# MOSFETs_and_Driver.net
KiCad netlist of a schematic drawn in Altium Designer
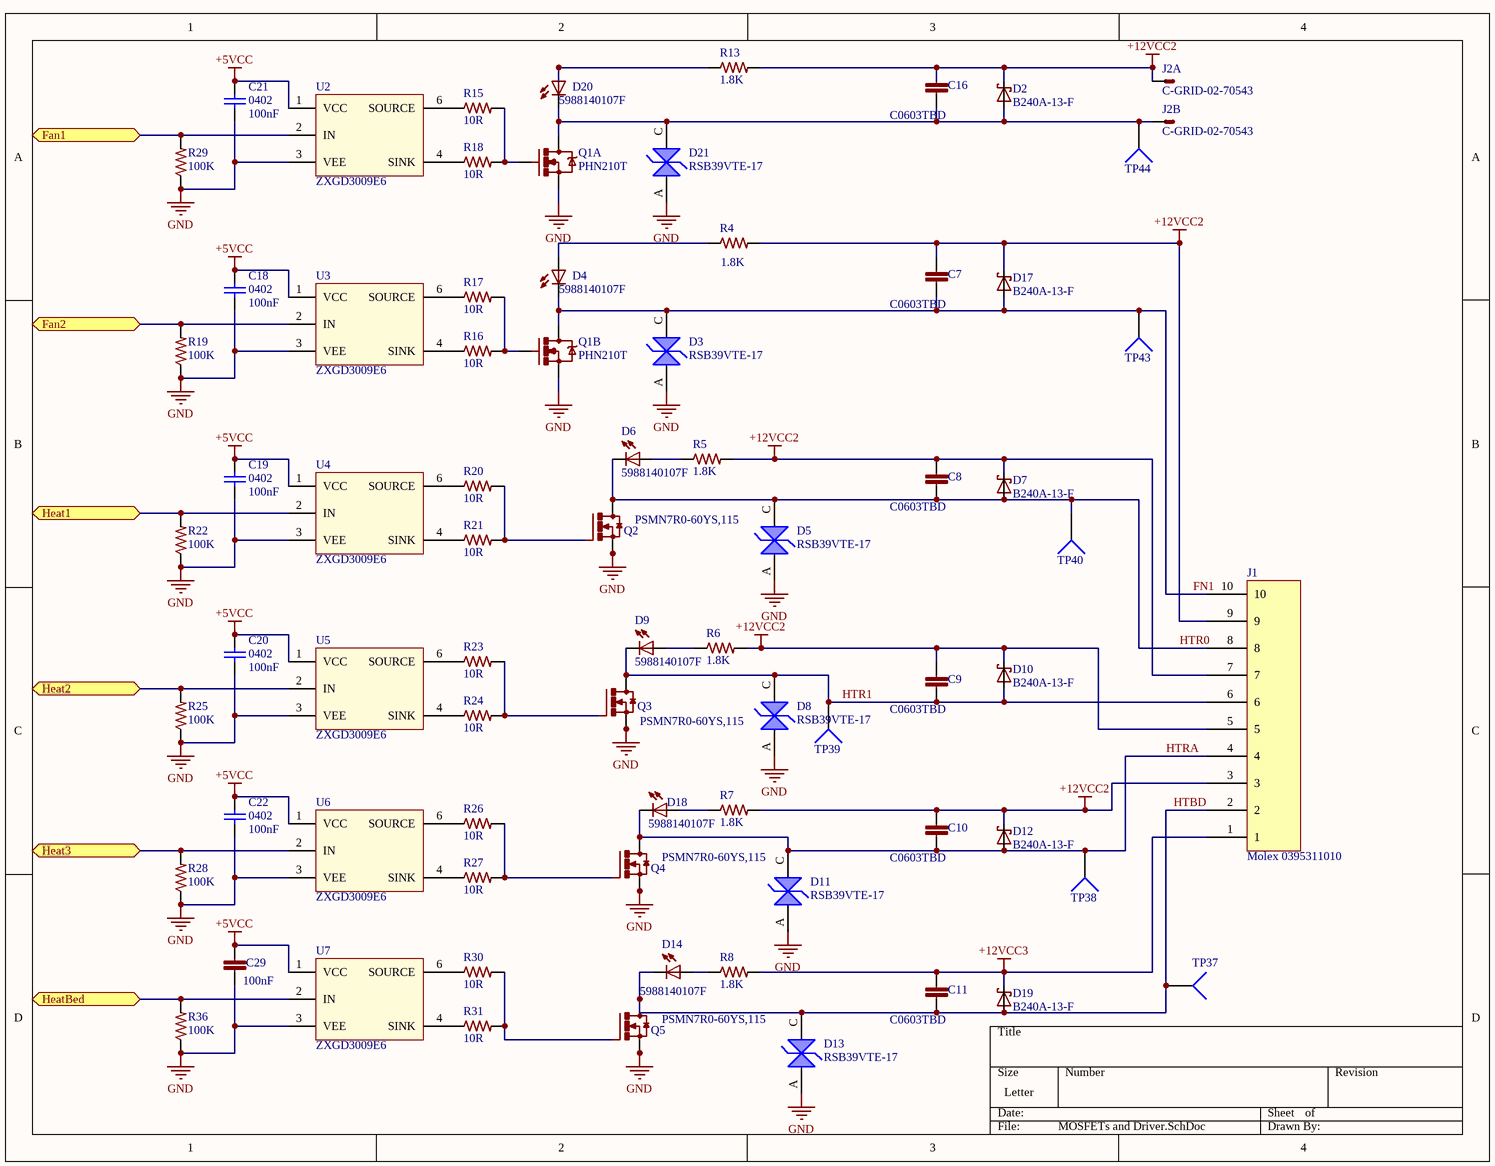
[diagram p0: MOSFETs and Driver.SchDoc]

(export (version "E")
  (design (tool "Eeschema 10.0.6"))
  (components
    (comp (ref "C7")
      (value "C0603TBD")
      (footprint "C0603")
      (description "Capacitor Non Polarized")
      (fields (field (name "PUBLISHER") "UltiMachine"))
      (libsource (lib "3Delight") (part "C0603TBD"))
    )
    (comp (ref "C8")
      (value "C0603TBD")
      (footprint "C0603")
      (description "Capacitor Non Polarized")
      (fields (field (name "PUBLISHER") "UltiMachine"))
      (libsource (lib "3Delight") (part "C0603TBD"))
    )
    (comp (ref "C9")
      (value "C0603TBD")
      (footprint "C0603")
      (description "Capacitor Non Polarized")
      (fields (field (name "PUBLISHER") "UltiMachine"))
      (libsource (lib "3Delight") (part "C0603TBD"))
    )
    (comp (ref "C10")
      (value "C0603TBD")
      (footprint "C0603")
      (description "Capacitor Non Polarized")
      (fields (field (name "PUBLISHER") "UltiMachine"))
      (libsource (lib "3Delight") (part "C0603TBD"))
    )
    (comp (ref "C11")
      (value "C0603TBD")
      (footprint "C0603")
      (description "Capacitor Non Polarized")
      (fields (field (name "PUBLISHER") "UltiMachine"))
      (libsource (lib "3Delight") (part "C0603TBD"))
    )
    (comp (ref "C16")
      (value "C0603TBD")
      (footprint "C0603")
      (description "Capacitor Non Polarized")
      (fields (field (name "PUBLISHER") "UltiMachine"))
      (libsource (lib "3Delight") (part "C0603TBD"))
    )
    (comp (ref "C18")
      (value "100nF")
      (footprint "C0402")
      (description "CAP CER 0.1UF (100nF) 16V 10% X7R 0402")
      (fields
        (field (name "MFR PART #") "GRM155R71C104KA88D")
        (field (name "MFR") "Murata")
        (field (name "PACKAGEREFERENCE") "0402")
        (field (name "PUBLISHER") "Ultimachine")
      )
      (libsource (lib "3Delight") (part "GRM155R71C104KA88D"))
    )
    (comp (ref "C19")
      (value "100nF")
      (footprint "C0402")
      (description "CAP CER 0.1UF (100nF) 16V 10% X7R 0402")
      (fields
        (field (name "MFR PART #") "GRM155R71C104KA88D")
        (field (name "MFR") "Murata")
        (field (name "PACKAGEREFERENCE") "0402")
        (field (name "PUBLISHER") "Ultimachine")
      )
      (libsource (lib "3Delight") (part "GRM155R71C104KA88D"))
    )
    (comp (ref "C20")
      (value "100nF")
      (footprint "C0402")
      (description "CAP CER 0.1UF (100nF) 16V 10% X7R 0402")
      (fields
        (field (name "MFR PART #") "GRM155R71C104KA88D")
        (field (name "MFR") "Murata")
        (field (name "PACKAGEREFERENCE") "0402")
        (field (name "PUBLISHER") "Ultimachine")
      )
      (libsource (lib "3Delight") (part "GRM155R71C104KA88D"))
    )
    (comp (ref "C21")
      (value "100nF")
      (footprint "C0402")
      (description "CAP CER 0.1UF (100nF) 16V 10% X7R 0402")
      (fields
        (field (name "MFR PART #") "GRM155R71C104KA88D")
        (field (name "MFR") "Murata")
        (field (name "PACKAGEREFERENCE") "0402")
        (field (name "PUBLISHER") "Ultimachine")
      )
      (libsource (lib "3Delight") (part "GRM155R71C104KA88D"))
    )
    (comp (ref "C22")
      (value "100nF")
      (footprint "C0402")
      (description "CAP CER 0.1UF (100nF) 16V 10% X7R 0402")
      (fields
        (field (name "MFR PART #") "GRM155R71C104KA88D")
        (field (name "MFR") "Murata")
        (field (name "PACKAGEREFERENCE") "0402")
        (field (name "PUBLISHER") "Ultimachine")
      )
      (libsource (lib "3Delight") (part "GRM155R71C104KA88D"))
    )
    (comp (ref "C29")
      (value "100nF")
      (footprint "C0402")
      (description "CAP CER 0402 100nF 16V 10% X7R")
      (fields
        (field (name "MANUFACTURERPARTNUMBER") "GRM155R71C104KA88D")
        (field (name "PUBLISHER") "UltiMachine")
      )
      (libsource (lib "") (part "GRM155R71C104KA88D_1"))
    )
    (comp (ref "D2")
      (value "B240A-13-F")
      (footprint "SMA-SM")
      (description "DIODE Schottky 3A SMA")
      (fields (field (name "MANUFACTURERPARTNUMBER") "SK310A") (field (name "PUBLISHER") "UltiMachine"))
      (libsource (lib "3Delight") (part "SK310A"))
    )
    (comp (ref "D3")
      (value "RSB39VTE-17")
      (footprint "SOD323-R")
      (description "DIODE TVS")
      (libsource (lib "3Delight") (part "RSB39VTE-17"))
    )
    (comp (ref "D4")
      (value "5988140107F")
      (footprint "LED2012120")
      (description "LED 0805 Yellow")
      (fields (field (name "PUBLISHER") "UltiMachine"))
      (libsource (lib "3Delight") (part "5988140107F"))
    )
    (comp (ref "D5")
      (value "RSB39VTE-17")
      (footprint "SOD323-R")
      (description "DIODE TVS")
      (libsource (lib "3Delight") (part "RSB39VTE-17"))
    )
    (comp (ref "D6")
      (value "5988140107F")
      (footprint "LED2012120")
      (description "LED 0805 Yellow")
      (fields (field (name "PUBLISHER") "UltiMachine"))
      (libsource (lib "3Delight") (part "5988140107F"))
    )
    (comp (ref "D7")
      (value "B240A-13-F")
      (footprint "SMA-SM")
      (description "DIODE Schottky 3A SMA")
      (fields (field (name "MANUFACTURERPARTNUMBER") "SK310A") (field (name "PUBLISHER") "UltiMachine"))
      (libsource (lib "3Delight") (part "SK310A"))
    )
    (comp (ref "D8")
      (value "RSB39VTE-17")
      (footprint "SOD323-R")
      (description "DIODE TVS")
      (libsource (lib "3Delight") (part "RSB39VTE-17"))
    )
    (comp (ref "D9")
      (value "5988140107F")
      (footprint "LED2012120")
      (description "LED 0805 Yellow")
      (fields (field (name "PUBLISHER") "UltiMachine"))
      (libsource (lib "3Delight") (part "5988140107F"))
    )
    (comp (ref "D10")
      (value "B240A-13-F")
      (footprint "SMA-SM")
      (description "DIODE Schottky 3A SMA")
      (fields (field (name "MANUFACTURERPARTNUMBER") "SK310A") (field (name "PUBLISHER") "UltiMachine"))
      (libsource (lib "3Delight") (part "SK310A"))
    )
    (comp (ref "D11")
      (value "RSB39VTE-17")
      (footprint "SOD323-R")
      (description "DIODE TVS")
      (libsource (lib "3Delight") (part "RSB39VTE-17"))
    )
    (comp (ref "D12")
      (value "B240A-13-F")
      (footprint "SMA-SM")
      (description "DIODE Schottky 3A SMA")
      (fields (field (name "MANUFACTURERPARTNUMBER") "SK310A") (field (name "PUBLISHER") "UltiMachine"))
      (libsource (lib "3Delight") (part "SK310A"))
    )
    (comp (ref "D13")
      (value "RSB39VTE-17")
      (footprint "SOD323-R")
      (description "DIODE TVS")
      (libsource (lib "3Delight") (part "RSB39VTE-17"))
    )
    (comp (ref "D14")
      (value "5988140107F")
      (footprint "LED2012120")
      (description "LED 0805 Yellow")
      (fields (field (name "PUBLISHER") "UltiMachine"))
      (libsource (lib "3Delight") (part "5988140107F"))
    )
    (comp (ref "D17")
      (value "B240A-13-F")
      (footprint "SMA-SM")
      (description "DIODE Schottky 3A SMA")
      (fields (field (name "MANUFACTURERPARTNUMBER") "SK310A") (field (name "PUBLISHER") "UltiMachine"))
      (libsource (lib "3Delight") (part "SK310A"))
    )
    (comp (ref "D18")
      (value "5988140107F")
      (footprint "LED2012120")
      (description "LED 0805 Yellow")
      (fields (field (name "PUBLISHER") "UltiMachine"))
      (libsource (lib "3Delight") (part "5988140107F"))
    )
    (comp (ref "D19")
      (value "B240A-13-F")
      (footprint "SMA-SM")
      (description "DIODE Schottky 3A SMA")
      (fields (field (name "MANUFACTURERPARTNUMBER") "SK310A") (field (name "PUBLISHER") "UltiMachine"))
      (libsource (lib "3Delight") (part "SK310A"))
    )
    (comp (ref "D20")
      (value "5988140107F")
      (footprint "LED2012120")
      (description "LED 0805 Yellow")
      (fields (field (name "PUBLISHER") "UltiMachine"))
      (libsource (lib "3Delight") (part "5988140107F"))
    )
    (comp (ref "D21")
      (value "RSB39VTE-17")
      (footprint "SOD323-R")
      (description "DIODE TVS")
      (libsource (lib "3Delight") (part "RSB39VTE-17"))
    )
    (comp (ref "J1")
      (value "Molex 0395311010")
      (footprint "MSTBV10")
      (description "MSBTV10 10 port connector same as RAMBo")
      (fields (field (name "PART NUMBER") "0395311010"))
      (libsource (lib "Tigershark3D") (part "0395311010 - Molex 10 Position Connector"))
    )
    (comp (ref "J2")
      (value "C-GRID-02-70543")
      (footprint "70543-02")
      (description "Connector 2pos")
      (fields (field (name "PUBLISHER") "UltiMachine"))
      (libsource (lib "3Delight") (part "C-GRID-02-70543"))
    )
    (comp (ref "Q1")
      (value "PHN210T")
      (footprint "SOIC8-dual-drain")
      (description "Dual N-channel TrenchMOS intermediate level FET")
      (libsource (lib "3Delight") (part "PHN210T"))
    )
    (comp (ref "Q2")
      (value "PSMN7R0-60YS,115")
      (footprint "SOT669")
      (description "Mosfet N-channel 60V 356A 117W 9.3mOhms")
      (fields (field (name "PUBLISHER") "UltiMachine"))
      (libsource (lib "3Delight") (part "PSMN7R0-60YS,115"))
    )
    (comp (ref "Q3")
      (value "PSMN7R0-60YS,115")
      (footprint "SOT669")
      (description "Mosfet N-channel 60V 356A 117W 9.3mOhms")
      (fields (field (name "PUBLISHER") "UltiMachine"))
      (libsource (lib "3Delight") (part "PSMN7R0-60YS,115"))
    )
    (comp (ref "Q4")
      (value "PSMN7R0-60YS,115")
      (footprint "SOT669")
      (description "Mosfet N-channel 60V 356A 117W 9.3mOhms")
      (fields (field (name "PUBLISHER") "UltiMachine"))
      (libsource (lib "3Delight") (part "PSMN7R0-60YS,115"))
    )
    (comp (ref "Q5")
      (value "PSMN7R0-60YS,115")
      (footprint "SOT669")
      (description "Mosfet N-channel 60V 356A 117W 9.3mOhms")
      (fields (field (name "PUBLISHER") "UltiMachine"))
      (libsource (lib "3Delight") (part "PSMN7R0-60YS,115"))
    )
    (comp (ref "R4")
      (value "1.8K")
      (footprint "R0603")
      (description "RES 0603 1.8K 100mW 5%")
      (fields
        (field (name "MANUFACTURERPARTNUMBER") "RC0603JR-071K8L")
        (field (name "PUBLISHER") "UltiMachine")
      )
      (libsource (lib "3Delight") (part "RC0603JR-071K8L"))
    )
    (comp (ref "R5")
      (value "1.8K")
      (footprint "R0603")
      (description "RES 0603 1.8K 100mW 5%")
      (fields
        (field (name "MANUFACTURERPARTNUMBER") "RC0603JR-071K8L")
        (field (name "PUBLISHER") "UltiMachine")
      )
      (libsource (lib "3Delight") (part "RC0603JR-071K8L"))
    )
    (comp (ref "R6")
      (value "1.8K")
      (footprint "R0603")
      (description "RES 0603 1.8K 100mW 5%")
      (fields
        (field (name "MANUFACTURERPARTNUMBER") "RC0603JR-071K8L")
        (field (name "PUBLISHER") "UltiMachine")
      )
      (libsource (lib "3Delight") (part "RC0603JR-071K8L"))
    )
    (comp (ref "R7")
      (value "1.8K")
      (footprint "R0603")
      (description "RES 0603 1.8K 100mW 5%")
      (fields
        (field (name "MANUFACTURERPARTNUMBER") "RC0603JR-071K8L")
        (field (name "PUBLISHER") "UltiMachine")
      )
      (libsource (lib "3Delight") (part "RC0603JR-071K8L"))
    )
    (comp (ref "R8")
      (value "1.8K")
      (footprint "R0603")
      (description "RES 0603 1.8K 100mW 5%")
      (fields
        (field (name "MANUFACTURERPARTNUMBER") "RC0603JR-071K8L")
        (field (name "PUBLISHER") "UltiMachine")
      )
      (libsource (lib "3Delight") (part "RC0603JR-071K8L"))
    )
    (comp (ref "R13")
      (value "1.8K")
      (footprint "R0603")
      (description "RES 0603 1.8K 100mW 5%")
      (fields
        (field (name "MANUFACTURERPARTNUMBER") "RC0603JR-071K8L")
        (field (name "PUBLISHER") "UltiMachine")
      )
      (libsource (lib "3Delight") (part "RC0603JR-071K8L"))
    )
    (comp (ref "R15")
      (value "10R")
      (footprint "R0402")
      (description "RES SMD 10K OHM 1% 1/16W 0402")
      (fields
        (field (name "MANUFACTURERPARTNUMBER") "RC0402FR-0710KP")
        (field (name "PUBLISHER") "UltiMachine")
      )
      (libsource (lib "3Delight") (part "RC0402FR-0710RL"))
    )
    (comp (ref "R16")
      (value "10R")
      (footprint "R0402")
      (description "RES SMD 10K OHM 1% 1/16W 0402")
      (fields
        (field (name "MANUFACTURERPARTNUMBER") "RC0402FR-0710KP")
        (field (name "PUBLISHER") "UltiMachine")
      )
      (libsource (lib "3Delight") (part "RC0402FR-0710RL"))
    )
    (comp (ref "R17")
      (value "10R")
      (footprint "R0402")
      (description "RES SMD 10K OHM 1% 1/16W 0402")
      (fields
        (field (name "MANUFACTURERPARTNUMBER") "RC0402FR-0710KP")
        (field (name "PUBLISHER") "UltiMachine")
      )
      (libsource (lib "3Delight") (part "RC0402FR-0710RL"))
    )
    (comp (ref "R18")
      (value "10R")
      (footprint "R0402")
      (description "RES SMD 10K OHM 1% 1/16W 0402")
      (fields
        (field (name "MANUFACTURERPARTNUMBER") "RC0402FR-0710KP")
        (field (name "PUBLISHER") "UltiMachine")
      )
      (libsource (lib "3Delight") (part "RC0402FR-0710RL"))
    )
    (comp (ref "R19")
      (value "100K")
      (footprint "3Delight:R0402")
      (description "RES SMD 100K OHM 1% 1/16W 0402")
      (fields
        (field (name "MANUFACTURER") "Samsung")
        (field (name "MANUFACTURERPARTNUMBER") "RC1005F104CS")
        (field (name "PUBLISHER") "UltiMachine")
      )
      (libsource (lib "Tigershark3D") (part "RC1005F104CS"))
    )
    (comp (ref "R20")
      (value "10R")
      (footprint "R0402")
      (description "RES SMD 10K OHM 1% 1/16W 0402")
      (fields
        (field (name "MANUFACTURERPARTNUMBER") "RC0402FR-0710KP")
        (field (name "PUBLISHER") "UltiMachine")
      )
      (libsource (lib "3Delight") (part "RC0402FR-0710RL"))
    )
    (comp (ref "R21")
      (value "10R")
      (footprint "R0402")
      (description "RES SMD 10K OHM 1% 1/16W 0402")
      (fields
        (field (name "MANUFACTURERPARTNUMBER") "RC0402FR-0710KP")
        (field (name "PUBLISHER") "UltiMachine")
      )
      (libsource (lib "3Delight") (part "RC0402FR-0710RL"))
    )
    (comp (ref "R22")
      (value "100K")
      (footprint "3Delight:R0402")
      (description "RES SMD 100K OHM 1% 1/16W 0402")
      (fields
        (field (name "MANUFACTURER") "Samsung")
        (field (name "MANUFACTURERPARTNUMBER") "RC1005F104CS")
        (field (name "PUBLISHER") "UltiMachine")
      )
      (libsource (lib "Tigershark3D") (part "RC1005F104CS"))
    )
    (comp (ref "R23")
      (value "10R")
      (footprint "R0402")
      (description "RES SMD 10K OHM 1% 1/16W 0402")
      (fields
        (field (name "MANUFACTURERPARTNUMBER") "RC0402FR-0710KP")
        (field (name "PUBLISHER") "UltiMachine")
      )
      (libsource (lib "3Delight") (part "RC0402FR-0710RL"))
    )
    (comp (ref "R24")
      (value "10R")
      (footprint "R0402")
      (description "RES SMD 10K OHM 1% 1/16W 0402")
      (fields
        (field (name "MANUFACTURERPARTNUMBER") "RC0402FR-0710KP")
        (field (name "PUBLISHER") "UltiMachine")
      )
      (libsource (lib "3Delight") (part "RC0402FR-0710RL"))
    )
    (comp (ref "R25")
      (value "100K")
      (footprint "3Delight:R0402")
      (description "RES SMD 100K OHM 1% 1/16W 0402")
      (fields
        (field (name "MANUFACTURER") "Samsung")
        (field (name "MANUFACTURERPARTNUMBER") "RC1005F104CS")
        (field (name "PUBLISHER") "UltiMachine")
      )
      (libsource (lib "Tigershark3D") (part "RC1005F104CS"))
    )
    (comp (ref "R26")
      (value "10R")
      (footprint "R0402")
      (description "RES SMD 10K OHM 1% 1/16W 0402")
      (fields
        (field (name "MANUFACTURERPARTNUMBER") "RC0402FR-0710KP")
        (field (name "PUBLISHER") "UltiMachine")
      )
      (libsource (lib "3Delight") (part "RC0402FR-0710RL"))
    )
    (comp (ref "R27")
      (value "10R")
      (footprint "R0402")
      (description "RES SMD 10K OHM 1% 1/16W 0402")
      (fields
        (field (name "MANUFACTURERPARTNUMBER") "RC0402FR-0710KP")
        (field (name "PUBLISHER") "UltiMachine")
      )
      (libsource (lib "3Delight") (part "RC0402FR-0710RL"))
    )
    (comp (ref "R28")
      (value "100K")
      (footprint "3Delight:R0402")
      (description "RES SMD 100K OHM 1% 1/16W 0402")
      (fields
        (field (name "MANUFACTURER") "Samsung")
        (field (name "MANUFACTURERPARTNUMBER") "RC1005F104CS")
        (field (name "PUBLISHER") "UltiMachine")
      )
      (libsource (lib "Tigershark3D") (part "RC1005F104CS"))
    )
    (comp (ref "R29")
      (value "100K")
      (footprint "3Delight:R0402")
      (description "RES SMD 100K OHM 1% 1/16W 0402")
      (fields
        (field (name "MANUFACTURER") "Samsung")
        (field (name "MANUFACTURERPARTNUMBER") "RC1005F104CS")
        (field (name "PUBLISHER") "UltiMachine")
      )
      (libsource (lib "Tigershark3D") (part "RC1005F104CS"))
    )
    (comp (ref "R30")
      (value "10R")
      (footprint "R0402")
      (description "RES SMD 10K OHM 1% 1/16W 0402")
      (fields
        (field (name "MANUFACTURERPARTNUMBER") "RC0402FR-0710KP")
        (field (name "PUBLISHER") "UltiMachine")
      )
      (libsource (lib "3Delight") (part "RC0402FR-0710RL"))
    )
    (comp (ref "R31")
      (value "10R")
      (footprint "R0402")
      (description "RES SMD 10K OHM 1% 1/16W 0402")
      (fields
        (field (name "MANUFACTURERPARTNUMBER") "RC0402FR-0710KP")
        (field (name "PUBLISHER") "UltiMachine")
      )
      (libsource (lib "3Delight") (part "RC0402FR-0710RL"))
    )
    (comp (ref "R36")
      (value "100K")
      (footprint "R0402")
      (description "RES SMD 100K OHM 1% 1/16W 0402")
      (fields
        (field (name "MANUFACTURER") "Samsung")
        (field (name "MANUFACTURERPARTNUMBER") "RC1005F104CS")
        (field (name "PUBLISHER") "UltiMachine")
      )
      (libsource (lib "Tigershark3D") (part "RC1005F104CS"))
    )
    (comp (ref "TP37")
      (value "TP4")
      (footprint "TP-2")
      (description "Socket")
      (fields (field (name "PUBLISHER") "Altium Limited"))
      (libsource (lib "ZMBo Schematic Library") (part "Socket"))
    )
    (comp (ref "TP38")
      (value "TP4")
      (footprint "TP-2")
      (description "Socket")
      (fields (field (name "PUBLISHER") "Altium Limited"))
      (libsource (lib "ZMBo Schematic Library") (part "Socket"))
    )
    (comp (ref "TP39")
      (value "TP4")
      (footprint "TP-2")
      (description "Socket")
      (fields (field (name "PUBLISHER") "Altium Limited"))
      (libsource (lib "ZMBo Schematic Library") (part "Socket"))
    )
    (comp (ref "TP40")
      (value "TP4")
      (footprint "TP-2")
      (description "Socket")
      (fields (field (name "PUBLISHER") "Altium Limited"))
      (libsource (lib "ZMBo Schematic Library") (part "Socket"))
    )
    (comp (ref "TP43")
      (value "TP4")
      (footprint "TP-2")
      (description "Socket")
      (fields (field (name "PUBLISHER") "Altium Limited"))
      (libsource (lib "ZMBo Schematic Library") (part "Socket"))
    )
    (comp (ref "TP44")
      (value "TP4")
      (footprint "TP-2")
      (description "Socket")
      (fields (field (name "PUBLISHER") "Altium Limited"))
      (libsource (lib "ZMBo Schematic Library") (part "Socket"))
    )
    (comp (ref "U2")
      (value "ZXGD3009E6")
      (footprint "SOT26P285X140-6L")
      (description "MOSFET DRVR 3A 1-OUT High Speed Non-Inv6-Pin SOT-26 T/R")
      (libsource (lib "3Delight") (part "ZXGD3009E6"))
    )
    (comp (ref "U3")
      (value "ZXGD3009E6")
      (footprint "SOT26P285X140-6L")
      (description "MOSFET DRVR 3A 1-OUT High Speed Non-Inv6-Pin SOT-26 T/R")
      (libsource (lib "3Delight") (part "ZXGD3009E6"))
    )
    (comp (ref "U4")
      (value "ZXGD3009E6")
      (footprint "SOT26P285X140-6L")
      (description "MOSFET DRVR 3A 1-OUT High Speed Non-Inv6-Pin SOT-26 T/R")
      (libsource (lib "3Delight") (part "ZXGD3009E6"))
    )
    (comp (ref "U5")
      (value "ZXGD3009E6")
      (footprint "SOT26P285X140-6L")
      (description "MOSFET DRVR 3A 1-OUT High Speed Non-Inv6-Pin SOT-26 T/R")
      (libsource (lib "3Delight") (part "ZXGD3009E6"))
    )
    (comp (ref "U6")
      (value "ZXGD3009E6")
      (footprint "SOT26P285X140-6L")
      (description "MOSFET DRVR 3A 1-OUT High Speed Non-Inv6-Pin SOT-26 T/R")
      (libsource (lib "3Delight") (part "ZXGD3009E6"))
    )
    (comp (ref "U7")
      (value "ZXGD3009E6")
      (footprint "SOT26P285X140-6L")
      (description "MOSFET DRVR 3A 1-OUT High Speed Non-Inv6-Pin SOT-26 T/R")
      (libsource (lib "3Delight") (part "ZXGD3009E6"))
    )
  )
  (nets
    (net (code "1") (name "+5VCC") (class "Default")
      (node (ref "C18") (pin "2") (pinfunction "2_2") (pintype "passive"))
      (node (ref "C19") (pin "2") (pinfunction "2_2") (pintype "passive"))
      (node (ref "C20") (pin "2") (pinfunction "2_2") (pintype "passive"))
      (node (ref "C21") (pin "2") (pinfunction "2_2") (pintype "passive"))
      (node (ref "C22") (pin "2") (pinfunction "2_2") (pintype "passive"))
      (node (ref "C29") (pin "1") (pinfunction "1_1") (pintype "passive"))
      (node (ref "U2") (pin "1") (pinfunction "VCC_1") (pintype "power_in"))
      (node (ref "U3") (pin "1") (pinfunction "VCC_1") (pintype "power_in"))
      (node (ref "U4") (pin "1") (pinfunction "VCC_1") (pintype "power_in"))
      (node (ref "U5") (pin "1") (pinfunction "VCC_1") (pintype "power_in"))
      (node (ref "U6") (pin "1") (pinfunction "VCC_1") (pintype "power_in"))
      (node (ref "U7") (pin "1") (pinfunction "VCC_1") (pintype "power_in"))
    )
    (net (code "2") (name "+12VCC2") (class "Default")
      (node (ref "C10") (pin "1") (pinfunction "1_1") (pintype "passive"))
      (node (ref "C16") (pin "1") (pinfunction "1_1") (pintype "passive"))
      (node (ref "C7") (pin "1") (pinfunction "1_1") (pintype "passive"))
      (node (ref "C8") (pin "1") (pinfunction "1_1") (pintype "passive"))
      (node (ref "C9") (pin "1") (pinfunction "1_1") (pintype "passive"))
      (node (ref "D10") (pin "C") (pinfunction "C_C") (pintype "passive"))
      (node (ref "D12") (pin "C") (pinfunction "C_C") (pintype "passive"))
      (node (ref "D17") (pin "C") (pinfunction "C_C") (pintype "passive"))
      (node (ref "D2") (pin "C") (pinfunction "C_C") (pintype "passive"))
      (node (ref "D7") (pin "C") (pinfunction "C_C") (pintype "passive"))
      (node (ref "J1") (pin "3") (pinfunction "3_3") (pintype "passive"))
      (node (ref "J1") (pin "5") (pinfunction "5_5") (pintype "passive"))
      (node (ref "J1") (pin "7") (pinfunction "7_7") (pintype "passive"))
      (node (ref "J1") (pin "9") (pinfunction "9_9") (pintype "passive"))
      (node (ref "J2") (pin "1") (pinfunction "S_1") (pintype "passive"))
      (node (ref "R13") (pin "2") (pinfunction "2_2") (pintype "passive"))
      (node (ref "R4") (pin "2") (pinfunction "2_2") (pintype "passive"))
      (node (ref "R5") (pin "2") (pinfunction "2_2") (pintype "passive"))
      (node (ref "R6") (pin "2") (pinfunction "2_2") (pintype "passive"))
      (node (ref "R7") (pin "2") (pinfunction "2_2") (pintype "passive"))
    )
    (net (code "3") (name "+12VCC3") (class "Default")
      (node (ref "C11") (pin "1") (pinfunction "1_1") (pintype "passive"))
      (node (ref "D19") (pin "C") (pinfunction "C_C") (pintype "passive"))
      (node (ref "J1") (pin "1") (pinfunction "1_1") (pintype "passive"))
      (node (ref "R8") (pin "2") (pinfunction "2_2") (pintype "passive"))
    )
    (net (code "4") (name "/FN1") (class "Default")
      (node (ref "C7") (pin "2") (pinfunction "2_2") (pintype "passive"))
      (node (ref "D17") (pin "A") (pinfunction "A_A") (pintype "passive"))
      (node (ref "D3") (pin "C") (pinfunction "C_C") (pintype "power_in"))
      (node (ref "D4") (pin "C") (pinfunction "C_C") (pintype "passive"))
      (node (ref "J1") (pin "10") (pinfunction "10_10") (pintype "passive"))
      (node (ref "Q1") (pin "5") (pinfunction "D_5") (pintype "passive"))
      (node (ref "TP43") (pin "1") (pinfunction "1_1") (pintype "passive"))
    )
    (net (code "5") (name "/Fan1") (class "Default")
      (node (ref "R29") (pin "2") (pinfunction "2_2") (pintype "passive"))
      (node (ref "U2") (pin "2") (pinfunction "IN_2") (pintype "power_in"))
    )
    (net (code "6") (name "/Fan2") (class "Default")
      (node (ref "R19") (pin "2") (pinfunction "2_2") (pintype "passive"))
      (node (ref "U3") (pin "2") (pinfunction "IN_2") (pintype "power_in"))
    )
    (net (code "7") (name "/HTBD") (class "Default")
      (node (ref "C11") (pin "2") (pinfunction "2_2") (pintype "passive"))
      (node (ref "D13") (pin "C") (pinfunction "C_C") (pintype "power_in"))
      (node (ref "D14") (pin "C") (pinfunction "C_C") (pintype "passive"))
      (node (ref "D19") (pin "A") (pinfunction "A_A") (pintype "passive"))
      (node (ref "J1") (pin "2") (pinfunction "2_2") (pintype "passive"))
      (node (ref "Q5") (pin "MB") (pinfunction "D_MB") (pintype "passive"))
      (node (ref "TP37") (pin "1") (pinfunction "1_1") (pintype "passive"))
    )
    (net (code "8") (name "/HTR0") (class "Default")
      (node (ref "C8") (pin "2") (pinfunction "2_2") (pintype "passive"))
      (node (ref "D5") (pin "C") (pinfunction "C_C") (pintype "power_in"))
      (node (ref "D6") (pin "C") (pinfunction "C_C") (pintype "passive"))
      (node (ref "D7") (pin "A") (pinfunction "A_A") (pintype "passive"))
      (node (ref "J1") (pin "8") (pinfunction "8_8") (pintype "passive"))
      (node (ref "Q2") (pin "MB") (pinfunction "D_MB") (pintype "passive"))
      (node (ref "TP40") (pin "1") (pinfunction "1_1") (pintype "passive"))
    )
    (net (code "9") (name "/HTR1") (class "Default")
      (node (ref "C9") (pin "2") (pinfunction "2_2") (pintype "passive"))
      (node (ref "D10") (pin "A") (pinfunction "A_A") (pintype "passive"))
      (node (ref "D8") (pin "C") (pinfunction "C_C") (pintype "power_in"))
      (node (ref "D9") (pin "C") (pinfunction "C_C") (pintype "passive"))
      (node (ref "J1") (pin "6") (pinfunction "6_6") (pintype "passive"))
      (node (ref "Q3") (pin "MB") (pinfunction "D_MB") (pintype "passive"))
      (node (ref "TP39") (pin "1") (pinfunction "1_1") (pintype "passive"))
    )
    (net (code "10") (name "/HTRA") (class "Default")
      (node (ref "C10") (pin "2") (pinfunction "2_2") (pintype "passive"))
      (node (ref "D11") (pin "C") (pinfunction "C_C") (pintype "power_in"))
      (node (ref "D12") (pin "A") (pinfunction "A_A") (pintype "passive"))
      (node (ref "D18") (pin "C") (pinfunction "C_C") (pintype "passive"))
      (node (ref "J1") (pin "4") (pinfunction "4_4") (pintype "passive"))
      (node (ref "Q4") (pin "MB") (pinfunction "D_MB") (pintype "passive"))
      (node (ref "TP38") (pin "1") (pinfunction "1_1") (pintype "passive"))
    )
    (net (code "11") (name "/Heat1") (class "Default")
      (node (ref "R22") (pin "2") (pinfunction "2_2") (pintype "passive"))
      (node (ref "U4") (pin "2") (pinfunction "IN_2") (pintype "power_in"))
    )
    (net (code "12") (name "/Heat2") (class "Default")
      (node (ref "R25") (pin "2") (pinfunction "2_2") (pintype "passive"))
      (node (ref "U5") (pin "2") (pinfunction "IN_2") (pintype "power_in"))
    )
    (net (code "13") (name "/Heat3") (class "Default")
      (node (ref "R28") (pin "2") (pinfunction "2_2") (pintype "passive"))
      (node (ref "U6") (pin "2") (pinfunction "IN_2") (pintype "power_in"))
    )
    (net (code "14") (name "/HeatBed") (class "Default")
      (node (ref "R36") (pin "2") (pinfunction "2_2") (pintype "passive"))
      (node (ref "U7") (pin "2") (pinfunction "IN_2") (pintype "power_in"))
    )
    (net (code "15") (name "GND") (class "Default")
      (node (ref "C18") (pin "1") (pinfunction "1_1") (pintype "passive"))
      (node (ref "C19") (pin "1") (pinfunction "1_1") (pintype "passive"))
      (node (ref "C20") (pin "1") (pinfunction "1_1") (pintype "passive"))
      (node (ref "C21") (pin "1") (pinfunction "1_1") (pintype "passive"))
      (node (ref "C22") (pin "1") (pinfunction "1_1") (pintype "passive"))
      (node (ref "C29") (pin "2") (pinfunction "2_2") (pintype "passive"))
      (node (ref "D11") (pin "A") (pinfunction "A_A") (pintype "power_in"))
      (node (ref "D13") (pin "A") (pinfunction "A_A") (pintype "power_in"))
      (node (ref "D21") (pin "A") (pinfunction "A_A") (pintype "power_in"))
      (node (ref "D3") (pin "A") (pinfunction "A_A") (pintype "power_in"))
      (node (ref "D5") (pin "A") (pinfunction "A_A") (pintype "power_in"))
      (node (ref "D8") (pin "A") (pinfunction "A_A") (pintype "power_in"))
      (node (ref "Q1") (pin "1") (pinfunction "S_1") (pintype "passive"))
      (node (ref "Q1") (pin "3") (pinfunction "S_3") (pintype "passive"))
      (node (ref "Q2") (pin "1") (pinfunction "S_1") (pintype "passive"))
      (node (ref "Q2") (pin "2") (pinfunction "S_2") (pintype "passive"))
      (node (ref "Q2") (pin "3") (pinfunction "S_3") (pintype "passive"))
      (node (ref "Q3") (pin "1") (pinfunction "S_1") (pintype "passive"))
      (node (ref "Q3") (pin "2") (pinfunction "S_2") (pintype "passive"))
      (node (ref "Q3") (pin "3") (pinfunction "S_3") (pintype "passive"))
      (node (ref "Q4") (pin "1") (pinfunction "S_1") (pintype "passive"))
      (node (ref "Q4") (pin "2") (pinfunction "S_2") (pintype "passive"))
      (node (ref "Q4") (pin "3") (pinfunction "S_3") (pintype "passive"))
      (node (ref "Q5") (pin "1") (pinfunction "S_1") (pintype "passive"))
      (node (ref "Q5") (pin "2") (pinfunction "S_2") (pintype "passive"))
      (node (ref "Q5") (pin "3") (pinfunction "S_3") (pintype "passive"))
      (node (ref "R19") (pin "1") (pinfunction "1_1") (pintype "passive"))
      (node (ref "R22") (pin "1") (pinfunction "1_1") (pintype "passive"))
      (node (ref "R25") (pin "1") (pinfunction "1_1") (pintype "passive"))
      (node (ref "R28") (pin "1") (pinfunction "1_1") (pintype "passive"))
      (node (ref "R29") (pin "1") (pinfunction "1_1") (pintype "passive"))
      (node (ref "R36") (pin "1") (pinfunction "1_1") (pintype "passive"))
      (node (ref "U2") (pin "3") (pinfunction "VEE_3") (pintype "power_in"))
      (node (ref "U3") (pin "3") (pinfunction "VEE_3") (pintype "power_in"))
      (node (ref "U4") (pin "3") (pinfunction "VEE_3") (pintype "power_in"))
      (node (ref "U5") (pin "3") (pinfunction "VEE_3") (pintype "power_in"))
      (node (ref "U6") (pin "3") (pinfunction "VEE_3") (pintype "power_in"))
      (node (ref "U7") (pin "3") (pinfunction "VEE_3") (pintype "power_in"))
    )
    (net (code "16") (name "Net-(D4-PadA)") (class "Default")
      (node (ref "D4") (pin "A") (pinfunction "A_A") (pintype "passive"))
      (node (ref "R4") (pin "1") (pinfunction "1_1") (pintype "passive"))
    )
    (net (code "17") (name "Net-(D6-PadA)") (class "Default")
      (node (ref "D6") (pin "A") (pinfunction "A_A") (pintype "passive"))
      (node (ref "R5") (pin "1") (pinfunction "1_1") (pintype "passive"))
    )
    (net (code "18") (name "Net-(D9-PadA)") (class "Default")
      (node (ref "D9") (pin "A") (pinfunction "A_A") (pintype "passive"))
      (node (ref "R6") (pin "1") (pinfunction "1_1") (pintype "passive"))
    )
    (net (code "19") (name "Net-(D14-PadA)") (class "Default")
      (node (ref "D14") (pin "A") (pinfunction "A_A") (pintype "passive"))
      (node (ref "R8") (pin "1") (pinfunction "1_1") (pintype "passive"))
    )
    (net (code "20") (name "Net-(D18-PadA)") (class "Default")
      (node (ref "D18") (pin "A") (pinfunction "A_A") (pintype "passive"))
      (node (ref "R7") (pin "1") (pinfunction "1_1") (pintype "passive"))
    )
    (net (code "21") (name "Net-(D20-PadA)") (class "Default")
      (node (ref "D20") (pin "A") (pinfunction "A_A") (pintype "passive"))
      (node (ref "R13") (pin "1") (pinfunction "1_1") (pintype "passive"))
    )
    (net (code "22") (name "Net-(J2B-S)") (class "Default")
      (node (ref "C16") (pin "2") (pinfunction "2_2") (pintype "passive"))
      (node (ref "D2") (pin "A") (pinfunction "A_A") (pintype "passive"))
      (node (ref "D20") (pin "C") (pinfunction "C_C") (pintype "passive"))
      (node (ref "D21") (pin "C") (pinfunction "C_C") (pintype "power_in"))
      (node (ref "J2") (pin "2") (pinfunction "S_2") (pintype "passive"))
      (node (ref "Q1") (pin "7") (pinfunction "D_7") (pintype "passive"))
      (node (ref "TP44") (pin "1") (pinfunction "1_1") (pintype "passive"))
    )
    (net (code "23") (name "Net-(Q1A-G)") (class "Default")
      (node (ref "Q1") (pin "2") (pinfunction "G_2") (pintype "passive"))
      (node (ref "R15") (pin "2") (pinfunction "2_2") (pintype "passive"))
      (node (ref "R18") (pin "2") (pinfunction "2_2") (pintype "passive"))
    )
    (net (code "24") (name "Net-(Q1B-G)") (class "Default")
      (node (ref "Q1") (pin "4") (pinfunction "G_4") (pintype "passive"))
      (node (ref "R16") (pin "2") (pinfunction "2_2") (pintype "passive"))
      (node (ref "R17") (pin "2") (pinfunction "2_2") (pintype "passive"))
    )
    (net (code "25") (name "Net-(Q2-G)") (class "Default")
      (node (ref "Q2") (pin "4") (pinfunction "G_4") (pintype "passive"))
      (node (ref "R20") (pin "2") (pinfunction "2_2") (pintype "passive"))
      (node (ref "R21") (pin "2") (pinfunction "2_2") (pintype "passive"))
    )
    (net (code "26") (name "Net-(Q3-G)") (class "Default")
      (node (ref "Q3") (pin "4") (pinfunction "G_4") (pintype "passive"))
      (node (ref "R23") (pin "2") (pinfunction "2_2") (pintype "passive"))
      (node (ref "R24") (pin "2") (pinfunction "2_2") (pintype "passive"))
    )
    (net (code "27") (name "Net-(Q4-G)") (class "Default")
      (node (ref "Q4") (pin "4") (pinfunction "G_4") (pintype "passive"))
      (node (ref "R26") (pin "2") (pinfunction "2_2") (pintype "passive"))
      (node (ref "R27") (pin "2") (pinfunction "2_2") (pintype "passive"))
    )
    (net (code "28") (name "Net-(Q5-G)") (class "Default")
      (node (ref "Q5") (pin "4") (pinfunction "G_4") (pintype "passive"))
      (node (ref "R30") (pin "2") (pinfunction "2_2") (pintype "passive"))
      (node (ref "R31") (pin "2") (pinfunction "2_2") (pintype "passive"))
    )
    (net (code "29") (name "Net-(U2-SINK)") (class "Default")
      (node (ref "R18") (pin "1") (pinfunction "1_1") (pintype "passive"))
      (node (ref "U2") (pin "4") (pinfunction "SINK_4") (pintype "power_in"))
    )
    (net (code "30") (name "Net-(U2-SOURCE)") (class "Default")
      (node (ref "R15") (pin "1") (pinfunction "1_1") (pintype "passive"))
      (node (ref "U2") (pin "6") (pinfunction "SOURCE_6") (pintype "power_in"))
    )
    (net (code "31") (name "Net-(U3-SINK)") (class "Default")
      (node (ref "R16") (pin "1") (pinfunction "1_1") (pintype "passive"))
      (node (ref "U3") (pin "4") (pinfunction "SINK_4") (pintype "power_in"))
    )
    (net (code "32") (name "Net-(U3-SOURCE)") (class "Default")
      (node (ref "R17") (pin "1") (pinfunction "1_1") (pintype "passive"))
      (node (ref "U3") (pin "6") (pinfunction "SOURCE_6") (pintype "power_in"))
    )
    (net (code "33") (name "Net-(U4-SINK)") (class "Default")
      (node (ref "R21") (pin "1") (pinfunction "1_1") (pintype "passive"))
      (node (ref "U4") (pin "4") (pinfunction "SINK_4") (pintype "power_in"))
    )
    (net (code "34") (name "Net-(U4-SOURCE)") (class "Default")
      (node (ref "R20") (pin "1") (pinfunction "1_1") (pintype "passive"))
      (node (ref "U4") (pin "6") (pinfunction "SOURCE_6") (pintype "power_in"))
    )
    (net (code "35") (name "Net-(U5-SINK)") (class "Default")
      (node (ref "R24") (pin "1") (pinfunction "1_1") (pintype "passive"))
      (node (ref "U5") (pin "4") (pinfunction "SINK_4") (pintype "power_in"))
    )
    (net (code "36") (name "Net-(U5-SOURCE)") (class "Default")
      (node (ref "R23") (pin "1") (pinfunction "1_1") (pintype "passive"))
      (node (ref "U5") (pin "6") (pinfunction "SOURCE_6") (pintype "power_in"))
    )
    (net (code "37") (name "Net-(U6-SINK)") (class "Default")
      (node (ref "R27") (pin "1") (pinfunction "1_1") (pintype "passive"))
      (node (ref "U6") (pin "4") (pinfunction "SINK_4") (pintype "power_in"))
    )
    (net (code "38") (name "Net-(U6-SOURCE)") (class "Default")
      (node (ref "R26") (pin "1") (pinfunction "1_1") (pintype "passive"))
      (node (ref "U6") (pin "6") (pinfunction "SOURCE_6") (pintype "power_in"))
    )
    (net (code "39") (name "Net-(U7-SINK)") (class "Default")
      (node (ref "R31") (pin "1") (pinfunction "1_1") (pintype "passive"))
      (node (ref "U7") (pin "4") (pinfunction "SINK_4") (pintype "power_in"))
    )
    (net (code "40") (name "Net-(U7-SOURCE)") (class "Default")
      (node (ref "R30") (pin "1") (pinfunction "1_1") (pintype "passive"))
      (node (ref "U7") (pin "6") (pinfunction "SOURCE_6") (pintype "power_in"))
    )
  )
)
